# Mini_VFD_UI_RevA.net
KiCad netlist of a schematic drawn in EAGLE
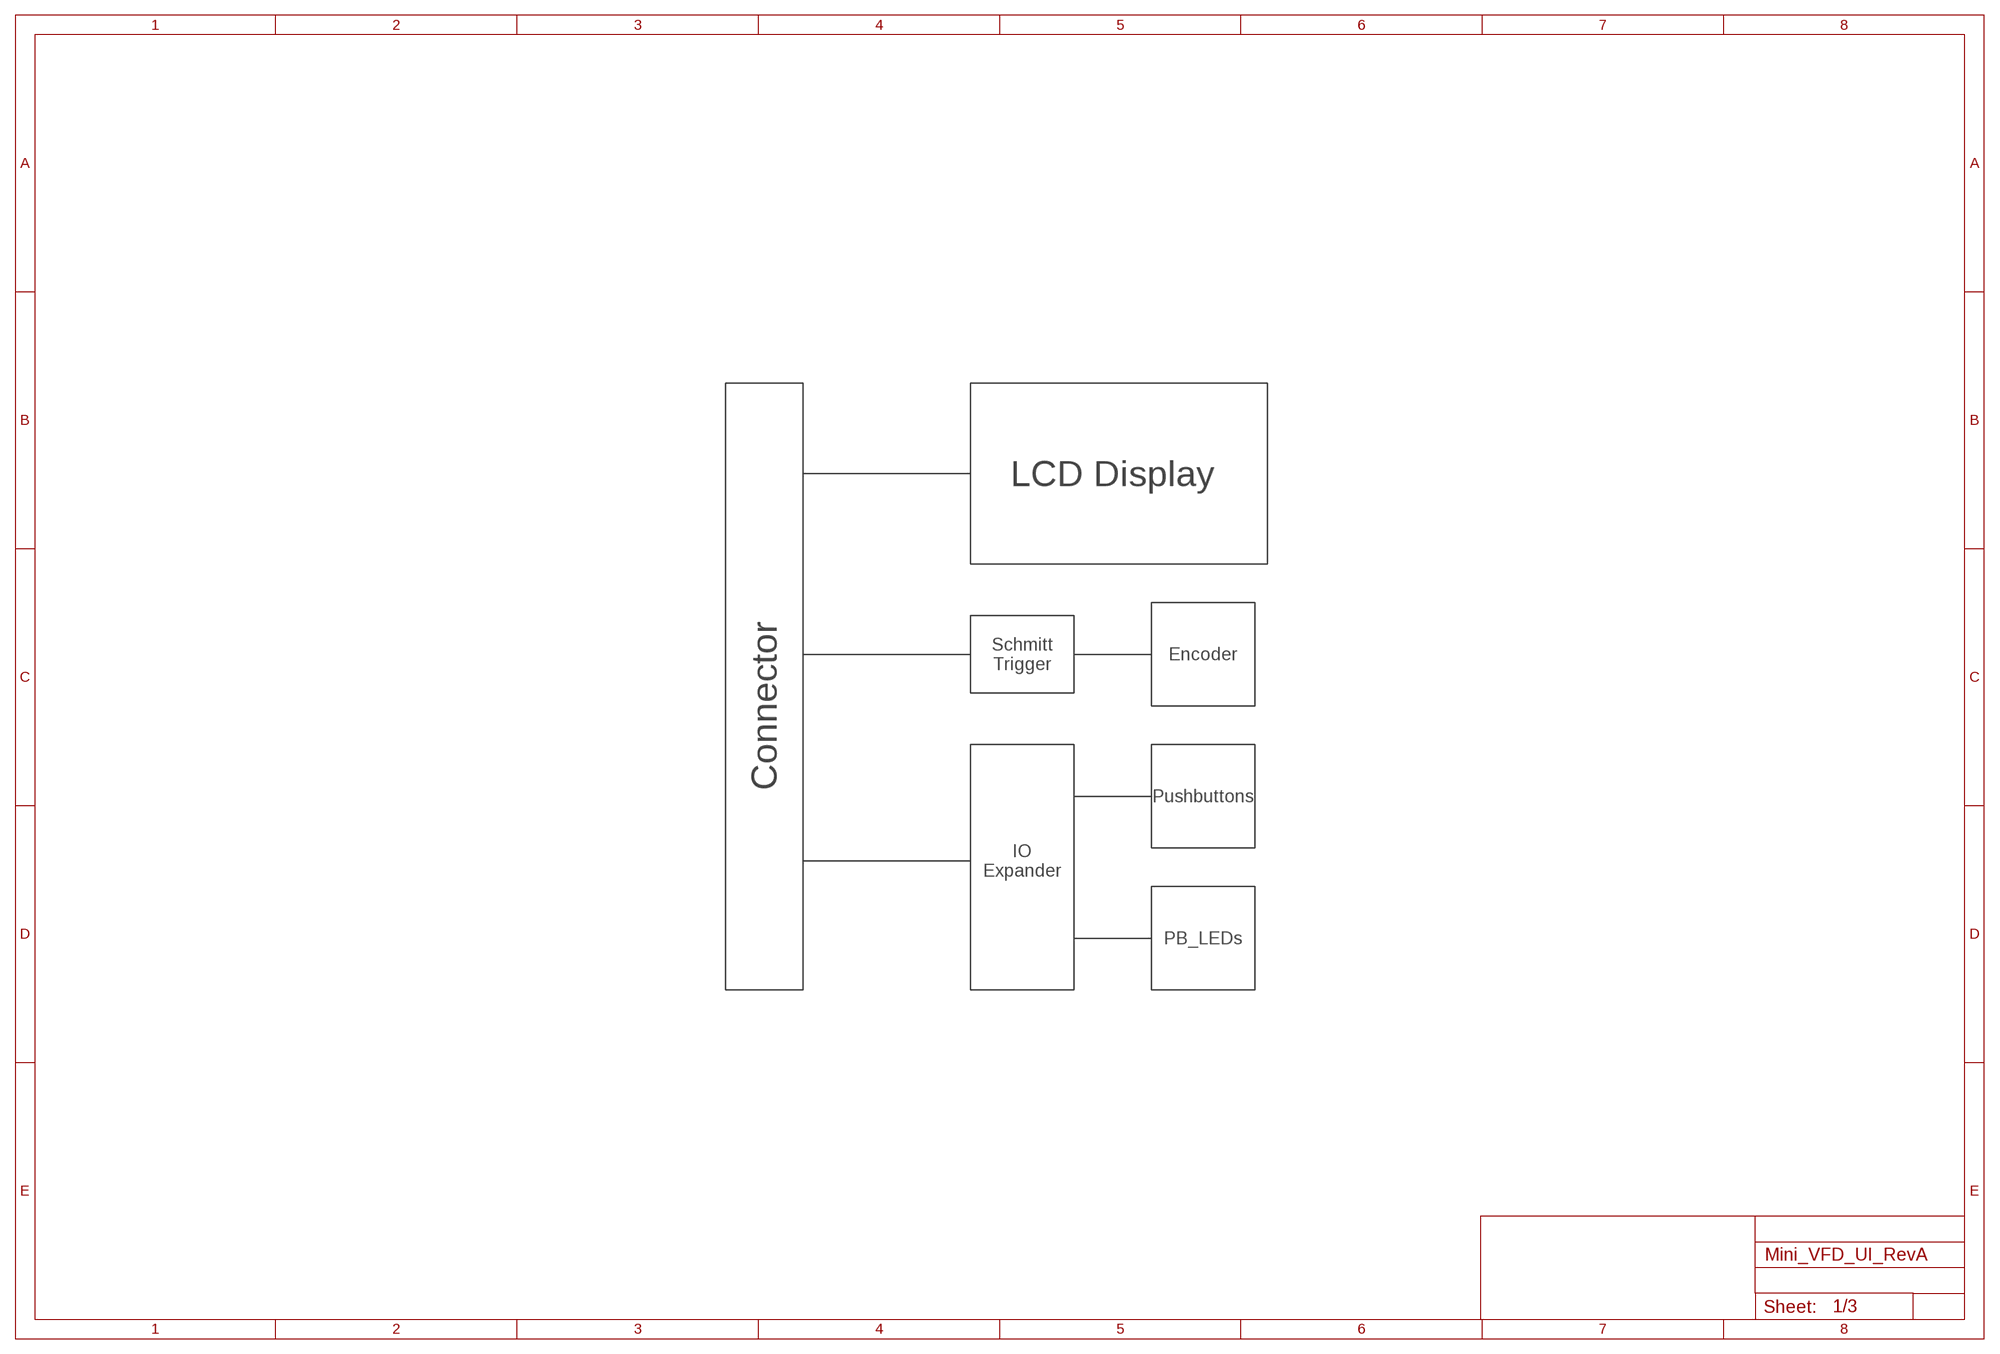
[diagram p0: schematic, sheet 1]
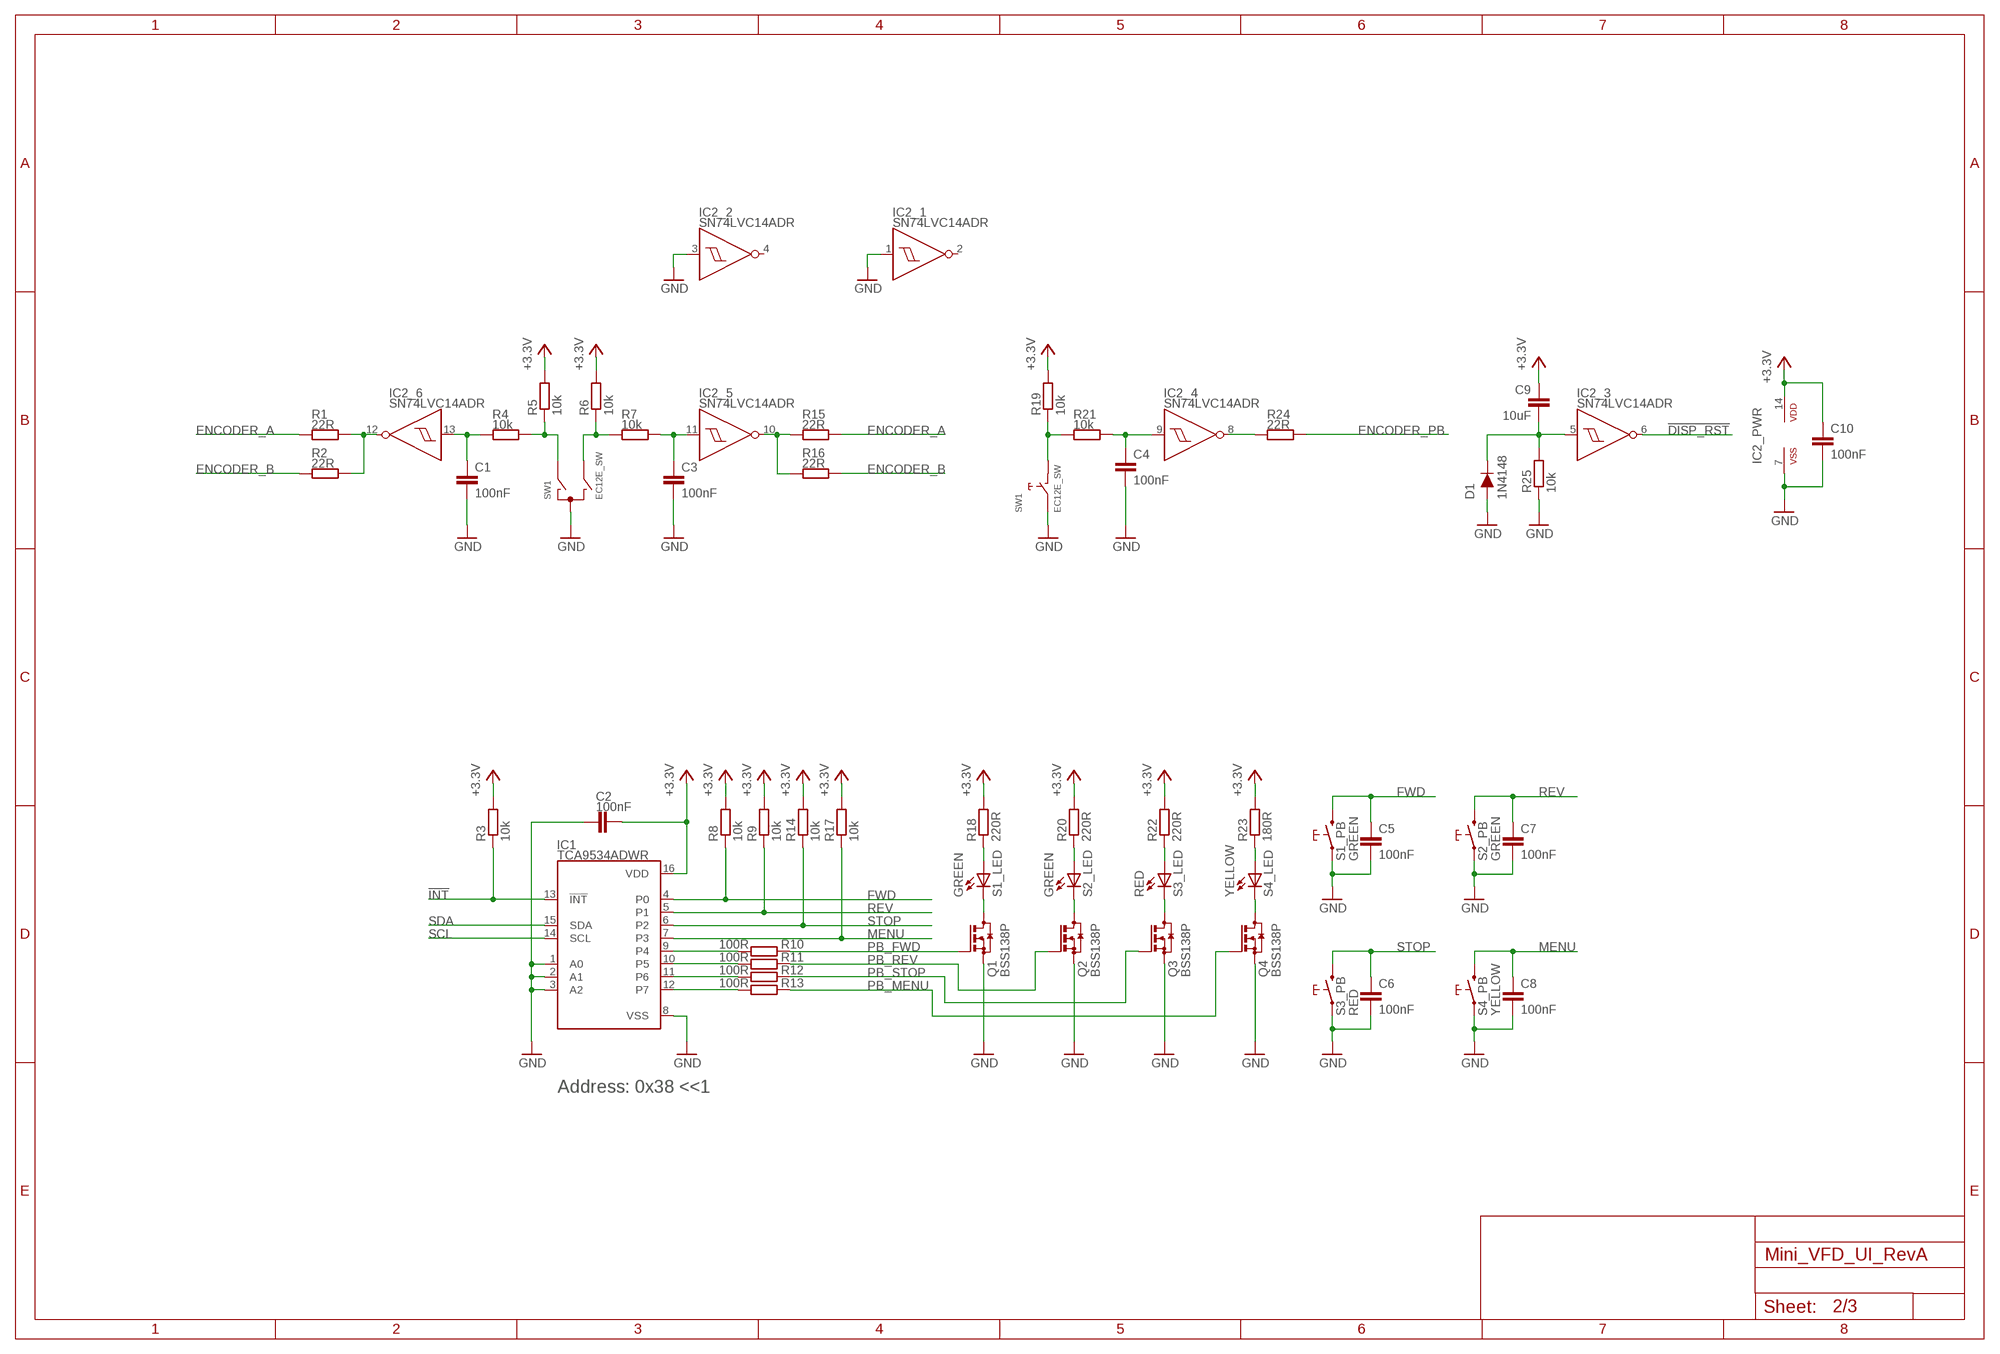
[diagram p1: schematic, sheet 2]
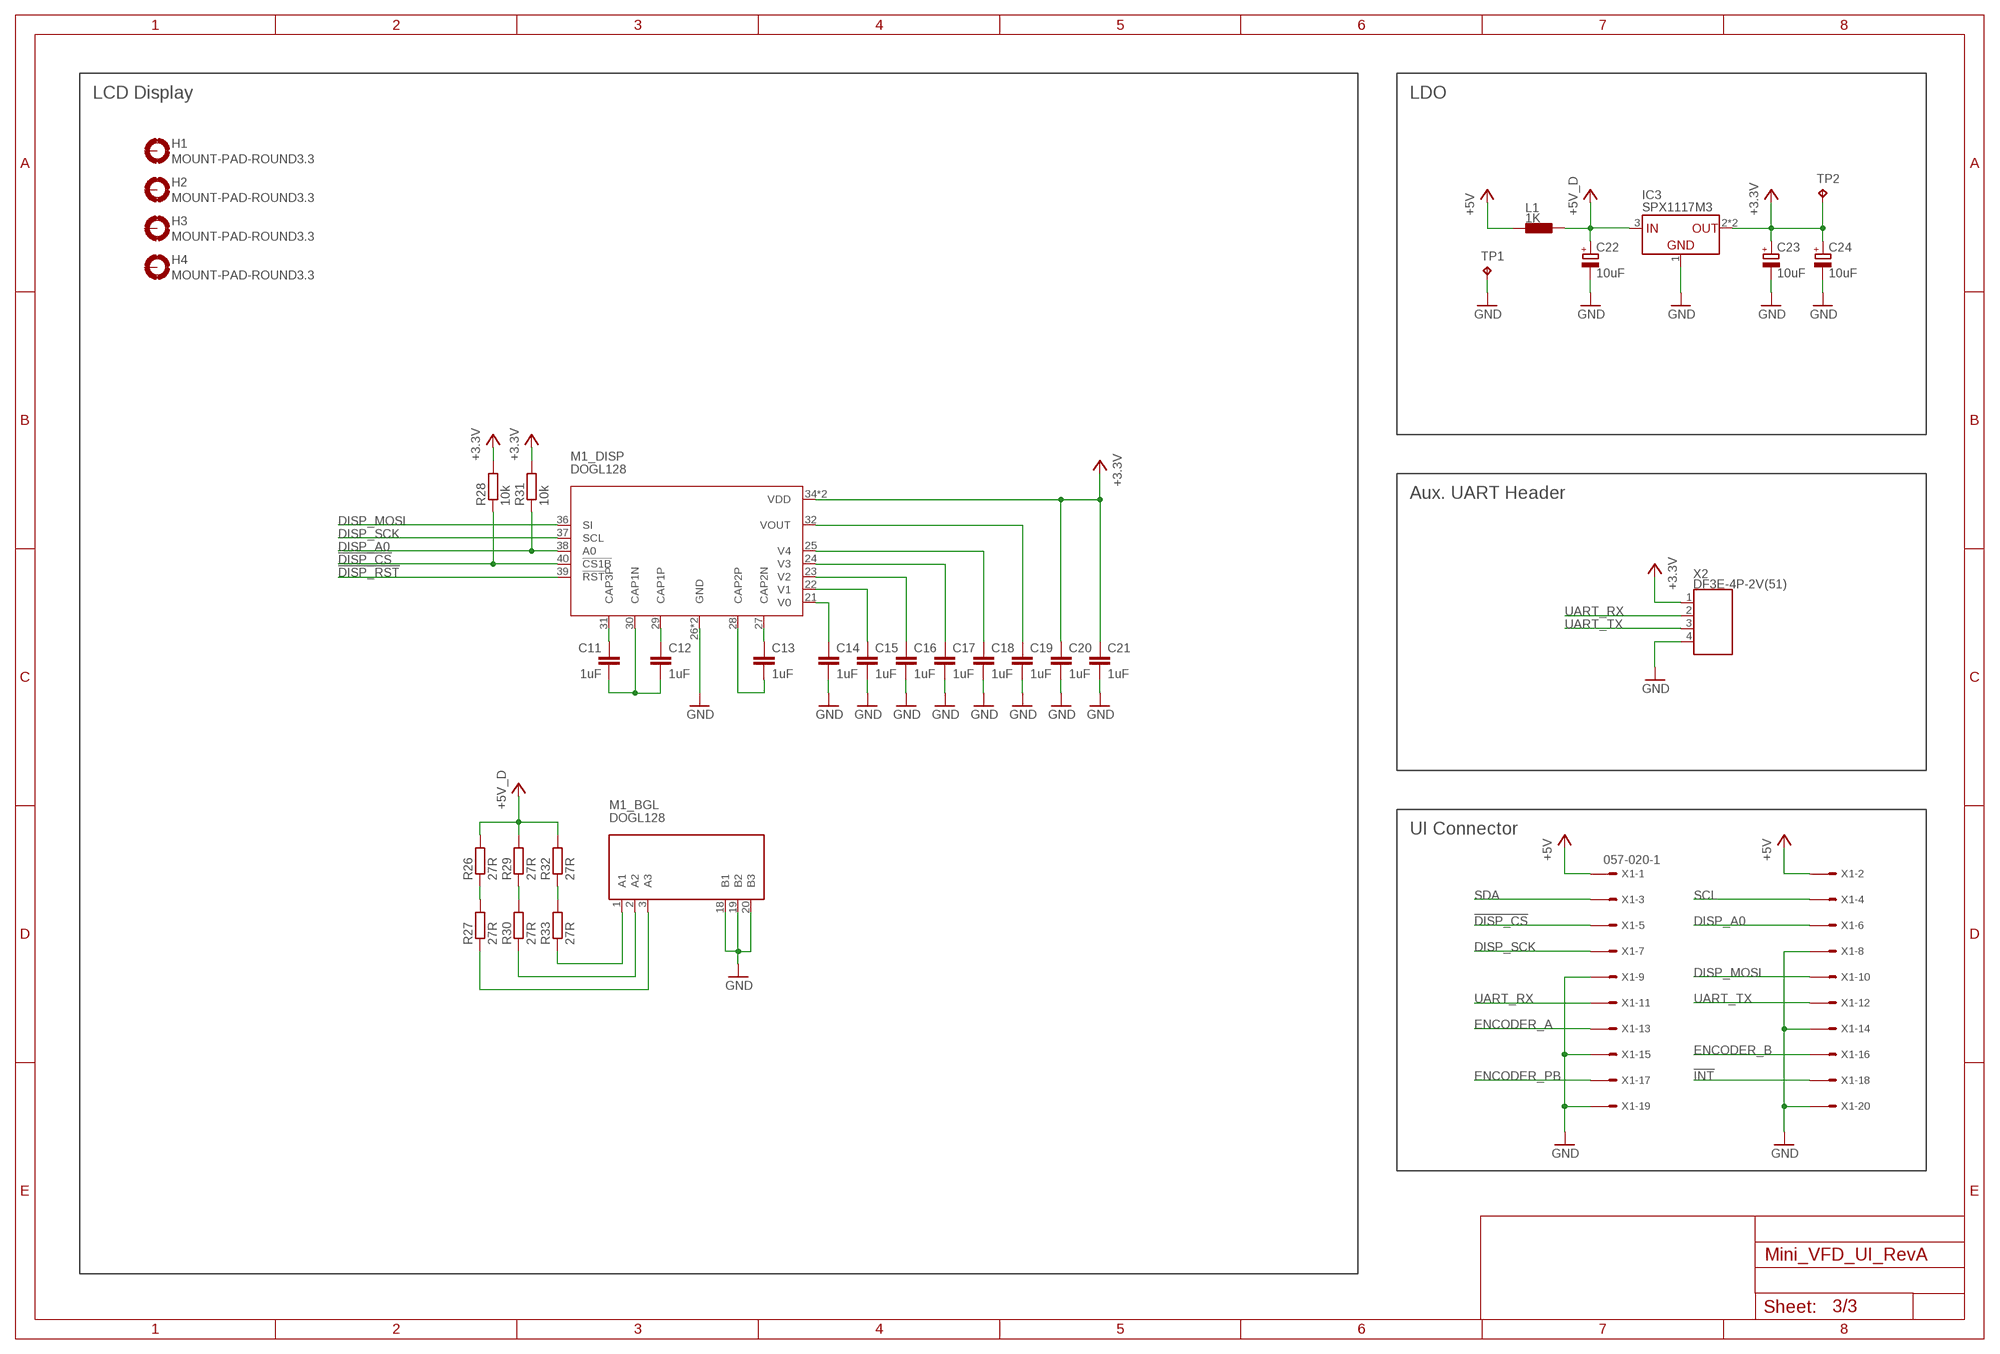
[diagram p2: schematic, sheet 3]

(export (version "E")
  (design (tool "Eeschema 10.0.6"))
  (components
    (comp (ref "C1")
      (value "100nF")
      (footprint "eagle-import:C0603")
      (libsource (lib "eagle-import") (part "C-EUC0603"))
    )
    (comp (ref "C2")
      (value "100nF")
      (footprint "eagle-import:C0603")
      (libsource (lib "eagle-import") (part "C-EUC0603"))
    )
    (comp (ref "C3")
      (value "100nF")
      (footprint "eagle-import:C0603")
      (libsource (lib "eagle-import") (part "C-EUC0603"))
    )
    (comp (ref "C4")
      (value "100nF")
      (footprint "eagle-import:C0603")
      (libsource (lib "eagle-import") (part "C-EUC0603"))
    )
    (comp (ref "C5")
      (value "100nF")
      (footprint "eagle-import:C0603")
      (libsource (lib "eagle-import") (part "C-EUC0603"))
    )
    (comp (ref "C6")
      (value "100nF")
      (footprint "eagle-import:C0603")
      (libsource (lib "eagle-import") (part "C-EUC0603"))
    )
    (comp (ref "C7")
      (value "100nF")
      (footprint "eagle-import:C0603")
      (libsource (lib "eagle-import") (part "C-EUC0603"))
    )
    (comp (ref "C8")
      (value "100nF")
      (footprint "eagle-import:C0603")
      (libsource (lib "eagle-import") (part "C-EUC0603"))
    )
    (comp (ref "C9")
      (value "10uF")
      (footprint "eagle-import:C1206")
      (libsource (lib "eagle-import") (part "C-EUC1206"))
    )
    (comp (ref "C10")
      (value "100nF")
      (footprint "eagle-import:C0603")
      (libsource (lib "eagle-import") (part "C-EUC0603"))
    )
    (comp (ref "D1")
      (value "1N4148")
      (footprint "eagle-import:SOD123")
      (libsource (lib "eagle-import") (part "DIODE"))
    )
    (comp (ref "IC1")
      (value "TCA9534ADWR")
      (footprint "eagle-import:SOIC16R")
      (libsource (lib "eagle-import") (part "TCA9534APWR_SOIC"))
    )
    (comp (ref "IC2")
      (value "SN74LVC14ADR")
      (footprint "eagle-import:SO14")
      (libsource (lib "eagle-import") (part "SN74AC14PWR_SOIC"))
    )
    (comp (ref "Q1")
      (value "BSS138P")
      (footprint "eagle-import:SOT23")
      (libsource (lib "eagle-import") (part "NMOS_BSS138P"))
    )
    (comp (ref "Q2")
      (value "BSS138P")
      (footprint "eagle-import:SOT23")
      (libsource (lib "eagle-import") (part "NMOS_BSS138P"))
    )
    (comp (ref "Q3")
      (value "BSS138P")
      (footprint "eagle-import:SOT23")
      (libsource (lib "eagle-import") (part "NMOS_BSS138P"))
    )
    (comp (ref "Q4")
      (value "BSS138P")
      (footprint "eagle-import:SOT23")
      (libsource (lib "eagle-import") (part "NMOS_BSS138P"))
    )
    (comp (ref "R1")
      (value "22R")
      (footprint "eagle-import:R0603")
      (libsource (lib "eagle-import") (part "R-EU_R0603"))
    )
    (comp (ref "R2")
      (value "22R")
      (footprint "eagle-import:R0603")
      (libsource (lib "eagle-import") (part "R-EU_R0603"))
    )
    (comp (ref "R3")
      (value "10k")
      (footprint "eagle-import:R0603")
      (libsource (lib "eagle-import") (part "R-EU_R0603"))
    )
    (comp (ref "R4")
      (value "10k")
      (footprint "eagle-import:R0603")
      (libsource (lib "eagle-import") (part "R-EU_R0603"))
    )
    (comp (ref "R5")
      (value "10k")
      (footprint "eagle-import:R0603")
      (libsource (lib "eagle-import") (part "R-EU_R0603"))
    )
    (comp (ref "R6")
      (value "10k")
      (footprint "eagle-import:R0603")
      (libsource (lib "eagle-import") (part "R-EU_R0603"))
    )
    (comp (ref "R7")
      (value "10k")
      (footprint "eagle-import:R0603")
      (libsource (lib "eagle-import") (part "R-EU_R0603"))
    )
    (comp (ref "R8")
      (value "10k")
      (footprint "eagle-import:R0603")
      (libsource (lib "eagle-import") (part "R-EU_R0603"))
    )
    (comp (ref "R9")
      (value "10k")
      (footprint "eagle-import:R0603")
      (libsource (lib "eagle-import") (part "R-EU_R0603"))
    )
    (comp (ref "R10")
      (value "100R")
      (footprint "eagle-import:R0603")
      (libsource (lib "eagle-import") (part "R-EU_R0603"))
    )
    (comp (ref "R11")
      (value "100R")
      (footprint "eagle-import:R0603")
      (libsource (lib "eagle-import") (part "R-EU_R0603"))
    )
    (comp (ref "R12")
      (value "100R")
      (footprint "eagle-import:R0603")
      (libsource (lib "eagle-import") (part "R-EU_R0603"))
    )
    (comp (ref "R13")
      (value "100R")
      (footprint "eagle-import:R0603")
      (libsource (lib "eagle-import") (part "R-EU_R0603"))
    )
    (comp (ref "R14")
      (value "10k")
      (footprint "eagle-import:R0603")
      (libsource (lib "eagle-import") (part "R-EU_R0603"))
    )
    (comp (ref "R15")
      (value "22R")
      (footprint "eagle-import:R0603")
      (libsource (lib "eagle-import") (part "R-EU_R0603"))
    )
    (comp (ref "R16")
      (value "22R")
      (footprint "eagle-import:R0603")
      (libsource (lib "eagle-import") (part "R-EU_R0603"))
    )
    (comp (ref "R17")
      (value "10k")
      (footprint "eagle-import:R0603")
      (libsource (lib "eagle-import") (part "R-EU_R0603"))
    )
    (comp (ref "R18")
      (value "220R")
      (footprint "eagle-import:R0603")
      (libsource (lib "eagle-import") (part "R-EU_R0603"))
    )
    (comp (ref "R19")
      (value "10k")
      (footprint "eagle-import:R0603")
      (libsource (lib "eagle-import") (part "R-EU_R0603"))
    )
    (comp (ref "R20")
      (value "220R")
      (footprint "eagle-import:R0603")
      (libsource (lib "eagle-import") (part "R-EU_R0603"))
    )
    (comp (ref "R21")
      (value "10k")
      (footprint "eagle-import:R0603")
      (libsource (lib "eagle-import") (part "R-EU_R0603"))
    )
    (comp (ref "R22")
      (value "220R")
      (footprint "eagle-import:R0603")
      (libsource (lib "eagle-import") (part "R-EU_R0603"))
    )
    (comp (ref "R23")
      (value "180R")
      (footprint "eagle-import:R0603")
      (libsource (lib "eagle-import") (part "R-EU_R0603"))
    )
    (comp (ref "R24")
      (value "22R")
      (footprint "eagle-import:R0603")
      (libsource (lib "eagle-import") (part "R-EU_R0603"))
    )
    (comp (ref "R25")
      (value "10k")
      (footprint "eagle-import:R0603")
      (libsource (lib "eagle-import") (part "R-EU_R0603"))
    )
    (comp (ref "S1")
      (value "GREEN")
      (footprint "eagle-import:PB_ALIEXPRESS")
      (libsource (lib "eagle-import") (part "PUSHBUTTON"))
    )
    (comp (ref "S2")
      (value "GREEN")
      (footprint "eagle-import:PB_ALIEXPRESS")
      (libsource (lib "eagle-import") (part "PUSHBUTTON"))
    )
    (comp (ref "S3")
      (value "RED")
      (footprint "eagle-import:PB_ALIEXPRESS")
      (libsource (lib "eagle-import") (part "PUSHBUTTON"))
    )
    (comp (ref "S4")
      (value "YELLOW")
      (footprint "eagle-import:PB_ALIEXPRESS")
      (libsource (lib "eagle-import") (part "PUSHBUTTON"))
    )
    (comp (ref "SW1")
      (value "EC12E_SW")
      (footprint "eagle-import:ALPS_EC12E_SW")
      (fields (field (name "MPN") "EC12E2424407"))
      (libsource (lib "eagle-import") (part "EC12E_SW"))
    )
    (comp (ref "C11")
      (value "1uF")
      (footprint "eagle-import:C0603")
      (libsource (lib "eagle-import") (part "C-EUC0603"))
    )
    (comp (ref "C12")
      (value "1uF")
      (footprint "eagle-import:C0603")
      (libsource (lib "eagle-import") (part "C-EUC0603"))
    )
    (comp (ref "C13")
      (value "1uF")
      (footprint "eagle-import:C0603")
      (libsource (lib "eagle-import") (part "C-EUC0603"))
    )
    (comp (ref "C14")
      (value "1uF")
      (footprint "eagle-import:C0603")
      (libsource (lib "eagle-import") (part "C-EUC0603"))
    )
    (comp (ref "C15")
      (value "1uF")
      (footprint "eagle-import:C0603")
      (libsource (lib "eagle-import") (part "C-EUC0603"))
    )
    (comp (ref "C16")
      (value "1uF")
      (footprint "eagle-import:C0603")
      (libsource (lib "eagle-import") (part "C-EUC0603"))
    )
    (comp (ref "C17")
      (value "1uF")
      (footprint "eagle-import:C0603")
      (libsource (lib "eagle-import") (part "C-EUC0603"))
    )
    (comp (ref "C18")
      (value "1uF")
      (footprint "eagle-import:C0603")
      (libsource (lib "eagle-import") (part "C-EUC0603"))
    )
    (comp (ref "C19")
      (value "1uF")
      (footprint "eagle-import:C0603")
      (libsource (lib "eagle-import") (part "C-EUC0603"))
    )
    (comp (ref "C20")
      (value "1uF")
      (footprint "eagle-import:C0603")
      (libsource (lib "eagle-import") (part "C-EUC0603"))
    )
    (comp (ref "C21")
      (value "1uF")
      (footprint "eagle-import:C0603")
      (libsource (lib "eagle-import") (part "C-EUC0603"))
    )
    (comp (ref "C22")
      (value "10uF")
      (footprint "eagle-import:CT3528")
      (libsource (lib "eagle-import") (part "CPOL-EUCT3528"))
    )
    (comp (ref "C23")
      (value "10uF")
      (footprint "eagle-import:CT3528")
      (libsource (lib "eagle-import") (part "CPOL-EUCT3528"))
    )
    (comp (ref "C24")
      (value "10uF")
      (footprint "eagle-import:CT3528")
      (libsource (lib "eagle-import") (part "CPOL-EUCT3528"))
    )
    (comp (ref "H1")
      (value "MOUNT-PAD-ROUND3.3")
      (footprint "eagle-import:3,3-PAD")
      (libsource (lib "eagle-import") (part "MOUNT-PAD-ROUND3.3"))
    )
    (comp (ref "H2")
      (value "MOUNT-PAD-ROUND3.3")
      (footprint "eagle-import:3,3-PAD")
      (libsource (lib "eagle-import") (part "MOUNT-PAD-ROUND3.3"))
    )
    (comp (ref "H3")
      (value "MOUNT-PAD-ROUND3.3")
      (footprint "eagle-import:3,3-PAD")
      (libsource (lib "eagle-import") (part "MOUNT-PAD-ROUND3.3"))
    )
    (comp (ref "H4")
      (value "MOUNT-PAD-ROUND3.3")
      (footprint "eagle-import:3,3-PAD")
      (libsource (lib "eagle-import") (part "MOUNT-PAD-ROUND3.3"))
    )
    (comp (ref "IC3")
      (value "SPX1117M3")
      (footprint "eagle-import:SOT223")
      (libsource (lib "eagle-import") (part "SPX1117_3V3"))
    )
    (comp (ref "L1")
      (value "1K")
      (footprint "eagle-import:R0603")
      (libsource (lib "eagle-import") (part "BEAD0603"))
    )
    (comp (ref "M1")
      (value "DOGL128")
      (footprint "eagle-import:DOGL128-6")
      (libsource (lib "eagle-import") (part "DOGL128"))
    )
    (comp (ref "R26")
      (value "27R")
      (footprint "eagle-import:R1206")
      (libsource (lib "eagle-import") (part "R-EU_R1206"))
    )
    (comp (ref "R27")
      (value "27R")
      (footprint "eagle-import:R1206")
      (libsource (lib "eagle-import") (part "R-EU_R1206"))
    )
    (comp (ref "R28")
      (value "10k")
      (footprint "eagle-import:R0603")
      (libsource (lib "eagle-import") (part "R-EU_R0603"))
    )
    (comp (ref "R29")
      (value "27R")
      (footprint "eagle-import:R1206")
      (libsource (lib "eagle-import") (part "R-EU_R1206"))
    )
    (comp (ref "R30")
      (value "27R")
      (footprint "eagle-import:R1206")
      (libsource (lib "eagle-import") (part "R-EU_R1206"))
    )
    (comp (ref "R31")
      (value "10k")
      (footprint "eagle-import:R0603")
      (libsource (lib "eagle-import") (part "R-EU_R0603"))
    )
    (comp (ref "R32")
      (value "27R")
      (footprint "eagle-import:R1206")
      (libsource (lib "eagle-import") (part "R-EU_R1206"))
    )
    (comp (ref "R33")
      (value "27R")
      (footprint "eagle-import:R1206")
      (libsource (lib "eagle-import") (part "R-EU_R1206"))
    )
    (comp (ref "TP1")
      (value "TPTP10R")
      (footprint "eagle-import:TP10R")
      (libsource (lib "eagle-import") (part "TPTP10R"))
    )
    (comp (ref "TP2")
      (value "TPTP10R")
      (footprint "eagle-import:TP10R")
      (libsource (lib "eagle-import") (part "TPTP10R"))
    )
    (comp (ref "X1")
      (value "057-020-1")
      (footprint "eagle-import:057-020-1")
      (libsource (lib "eagle-import") (part "057-020-1"))
    )
    (comp (ref "X2")
      (value "DF3E-4P-2V(51)")
      (footprint "eagle-import:DF3E-4P-2V")
      (libsource (lib "eagle-import") (part "DF3E-4P-2V"))
    )
  )
  (nets
    (net (code "1") (name "+3.3V") (class "Default")
      (node (ref "C10") (pin "1") (pinfunction "1_1") (pintype "passive"))
      (node (ref "C2") (pin "2") (pinfunction "2_2") (pintype "passive"))
      (node (ref "C20") (pin "1") (pinfunction "1_1") (pintype "passive"))
      (node (ref "C21") (pin "1") (pinfunction "1_1") (pintype "passive"))
      (node (ref "C23") (pin "+") (pinfunction "+_+") (pintype "passive"))
      (node (ref "C24") (pin "+") (pinfunction "+_+") (pintype "passive"))
      (node (ref "C9") (pin "1") (pinfunction "1_1") (pintype "passive"))
      (node (ref "IC1") (pin "16") (pinfunction "VDD_16") (pintype "input"))
      (node (ref "IC2") (pin "14") (pinfunction "VDD_14") (pintype "input"))
      (node (ref "IC3") (pin "2") (pinfunction "VOUT_2") (pintype "input"))
      (node (ref "IC3") (pin "4") (pinfunction "VOUT_4") (pintype "input"))
      (node (ref "M1") (pin "34") (pinfunction "VDD_34") (pintype "bidirectional"))
      (node (ref "M1") (pin "35") (pinfunction "VDD_35") (pintype "bidirectional"))
      (node (ref "R14") (pin "2") (pinfunction "2_2") (pintype "passive"))
      (node (ref "R17") (pin "2") (pinfunction "2_2") (pintype "passive"))
      (node (ref "R18") (pin "2") (pinfunction "2_2") (pintype "passive"))
      (node (ref "R19") (pin "2") (pinfunction "2_2") (pintype "passive"))
      (node (ref "R20") (pin "2") (pinfunction "2_2") (pintype "passive"))
      (node (ref "R22") (pin "2") (pinfunction "2_2") (pintype "passive"))
      (node (ref "R23") (pin "2") (pinfunction "2_2") (pintype "passive"))
      (node (ref "R28") (pin "2") (pinfunction "2_2") (pintype "passive"))
      (node (ref "R3") (pin "2") (pinfunction "2_2") (pintype "passive"))
      (node (ref "R31") (pin "2") (pinfunction "2_2") (pintype "passive"))
      (node (ref "R5") (pin "2") (pinfunction "2_2") (pintype "passive"))
      (node (ref "R6") (pin "2") (pinfunction "2_2") (pintype "passive"))
      (node (ref "R8") (pin "2") (pinfunction "2_2") (pintype "passive"))
      (node (ref "R9") (pin "2") (pinfunction "2_2") (pintype "passive"))
      (node (ref "TP2") (pin "TP") (pinfunction "TP_TP") (pintype "input"))
      (node (ref "X2") (pin "1") (pinfunction "1_1") (pintype "passive"))
    )
    (net (code "2") (name "+5V") (class "Default")
      (node (ref "L1") (pin "2") (pinfunction "2_2") (pintype "passive"))
      (node (ref "X1") (pin "1") (pinfunction "S_1") (pintype "passive"))
      (node (ref "X1") (pin "2") (pinfunction "S_2") (pintype "passive"))
    )
    (net (code "3") (name "+5V_D") (class "Default")
      (node (ref "C22") (pin "+") (pinfunction "+_+") (pintype "passive"))
      (node (ref "IC3") (pin "3") (pinfunction "VIN_3") (pintype "input"))
      (node (ref "L1") (pin "1") (pinfunction "1_1") (pintype "passive"))
      (node (ref "R26") (pin "2") (pinfunction "2_2") (pintype "passive"))
      (node (ref "R29") (pin "2") (pinfunction "2_2") (pintype "passive"))
      (node (ref "R32") (pin "2") (pinfunction "2_2") (pintype "passive"))
    )
    (net (code "4") (name "DISP_A0") (class "Default")
      (node (ref "M1") (pin "38") (pinfunction "A0_38") (pintype "bidirectional"))
      (node (ref "R31") (pin "1") (pinfunction "1_1") (pintype "passive"))
      (node (ref "X1") (pin "6") (pinfunction "S_6") (pintype "passive"))
    )
    (net (code "5") (name "DISP_MOSI") (class "Default")
      (node (ref "M1") (pin "36") (pinfunction "SI_36") (pintype "bidirectional"))
      (node (ref "X1") (pin "10") (pinfunction "S_10") (pintype "passive"))
    )
    (net (code "6") (name "DISP_SCK") (class "Default")
      (node (ref "M1") (pin "37") (pinfunction "SCL_37") (pintype "bidirectional"))
      (node (ref "X1") (pin "7") (pinfunction "S_7") (pintype "passive"))
    )
    (net (code "7") (name "ENCODER_A") (class "Default")
      (node (ref "R1") (pin "1") (pinfunction "1_1") (pintype "passive"))
      (node (ref "R15") (pin "2") (pinfunction "2_2") (pintype "passive"))
      (node (ref "X1") (pin "13") (pinfunction "S_13") (pintype "passive"))
    )
    (net (code "8") (name "ENCODER_B") (class "Default")
      (node (ref "R16") (pin "2") (pinfunction "2_2") (pintype "passive"))
      (node (ref "R2") (pin "1") (pinfunction "1_1") (pintype "passive"))
      (node (ref "X1") (pin "16") (pinfunction "S_16") (pintype "passive"))
    )
    (net (code "9") (name "ENCODER_PB") (class "Default")
      (node (ref "R24") (pin "2") (pinfunction "2_2") (pintype "passive"))
      (node (ref "X1") (pin "17") (pinfunction "S_17") (pintype "passive"))
    )
    (net (code "10") (name "FWD") (class "Default")
      (node (ref "C5") (pin "1") (pinfunction "1_1") (pintype "passive"))
      (node (ref "IC1") (pin "4") (pinfunction "P0_4") (pintype "bidirectional"))
      (node (ref "R8") (pin "1") (pinfunction "1_1") (pintype "passive"))
      (node (ref "S1") (pin "2A") (pinfunction "2_2A") (pintype "passive"))
      (node (ref "S1") (pin "2B") (pinfunction "2_2B") (pintype "passive"))
    )
    (net (code "11") (name "GND") (class "Default")
      (node (ref "C1") (pin "2") (pinfunction "2_2") (pintype "passive"))
      (node (ref "C10") (pin "2") (pinfunction "2_2") (pintype "passive"))
      (node (ref "C14") (pin "2") (pinfunction "2_2") (pintype "passive"))
      (node (ref "C15") (pin "2") (pinfunction "2_2") (pintype "passive"))
      (node (ref "C16") (pin "2") (pinfunction "2_2") (pintype "passive"))
      (node (ref "C17") (pin "2") (pinfunction "2_2") (pintype "passive"))
      (node (ref "C18") (pin "2") (pinfunction "2_2") (pintype "passive"))
      (node (ref "C19") (pin "2") (pinfunction "2_2") (pintype "passive"))
      (node (ref "C2") (pin "1") (pinfunction "1_1") (pintype "passive"))
      (node (ref "C20") (pin "2") (pinfunction "2_2") (pintype "passive"))
      (node (ref "C21") (pin "2") (pinfunction "2_2") (pintype "passive"))
      (node (ref "C22") (pin "-") (pinfunction "-_-") (pintype "passive"))
      (node (ref "C23") (pin "-") (pinfunction "-_-") (pintype "passive"))
      (node (ref "C24") (pin "-") (pinfunction "-_-") (pintype "passive"))
      (node (ref "C3") (pin "2") (pinfunction "2_2") (pintype "passive"))
      (node (ref "C4") (pin "2") (pinfunction "2_2") (pintype "passive"))
      (node (ref "C5") (pin "2") (pinfunction "2_2") (pintype "passive"))
      (node (ref "C6") (pin "2") (pinfunction "2_2") (pintype "passive"))
      (node (ref "C7") (pin "2") (pinfunction "2_2") (pintype "passive"))
      (node (ref "C8") (pin "2") (pinfunction "2_2") (pintype "passive"))
      (node (ref "D1") (pin "2") (pinfunction "A_2") (pintype "passive"))
      (node (ref "IC1") (pin "1") (pinfunction "A0_1") (pintype "input"))
      (node (ref "IC1") (pin "2") (pinfunction "A1_2") (pintype "input"))
      (node (ref "IC1") (pin "3") (pinfunction "A2_3") (pintype "input"))
      (node (ref "IC1") (pin "8") (pinfunction "VSS_8") (pintype "input"))
      (node (ref "IC2") (pin "1") (pinfunction "I_1") (pintype "input"))
      (node (ref "IC2") (pin "3") (pinfunction "I_3") (pintype "input"))
      (node (ref "IC2") (pin "7") (pinfunction "VSS_7") (pintype "input"))
      (node (ref "IC3") (pin "1") (pinfunction "GND_1") (pintype "input"))
      (node (ref "M1") (pin "18") (pinfunction "B1_18") (pintype "bidirectional"))
      (node (ref "M1") (pin "19") (pinfunction "B2_19") (pintype "bidirectional"))
      (node (ref "M1") (pin "20") (pinfunction "B3_20") (pintype "bidirectional"))
      (node (ref "M1") (pin "26") (pinfunction "GND_26") (pintype "bidirectional"))
      (node (ref "M1") (pin "33") (pinfunction "GND_33") (pintype "bidirectional"))
      (node (ref "Q1") (pin "2") (pinfunction "S_2") (pintype "passive"))
      (node (ref "Q2") (pin "2") (pinfunction "S_2") (pintype "passive"))
      (node (ref "Q3") (pin "2") (pinfunction "S_2") (pintype "passive"))
      (node (ref "Q4") (pin "2") (pinfunction "S_2") (pintype "passive"))
      (node (ref "R25") (pin "1") (pinfunction "1_1") (pintype "passive"))
      (node (ref "S1") (pin "1A") (pinfunction "1_1A") (pintype "passive"))
      (node (ref "S1") (pin "1B") (pinfunction "1_1B") (pintype "passive"))
      (node (ref "S2") (pin "1A") (pinfunction "1_1A") (pintype "passive"))
      (node (ref "S2") (pin "1B") (pinfunction "1_1B") (pintype "passive"))
      (node (ref "S3") (pin "1A") (pinfunction "1_1A") (pintype "passive"))
      (node (ref "S3") (pin "1B") (pinfunction "1_1B") (pintype "passive"))
      (node (ref "S4") (pin "1A") (pinfunction "1_1A") (pintype "passive"))
      (node (ref "S4") (pin "1B") (pinfunction "1_1B") (pintype "passive"))
      (node (ref "SW1") (pin "C") (pinfunction "C_C") (pintype "passive"))
      (node (ref "SW1") (pin "E") (pinfunction "2_E") (pintype "passive"))
      (node (ref "TP1") (pin "TP") (pinfunction "TP_TP") (pintype "input"))
      (node (ref "X1") (pin "14") (pinfunction "S_14") (pintype "passive"))
      (node (ref "X1") (pin "15") (pinfunction "S_15") (pintype "passive"))
      (node (ref "X1") (pin "19") (pinfunction "S_19") (pintype "passive"))
      (node (ref "X1") (pin "20") (pinfunction "S_20") (pintype "passive"))
      (node (ref "X1") (pin "8") (pinfunction "S_8") (pintype "passive"))
      (node (ref "X1") (pin "9") (pinfunction "S_9") (pintype "passive"))
      (node (ref "X2") (pin "4") (pinfunction "4_4") (pintype "passive"))
    )
    (net (code "12") (name "MENU") (class "Default")
      (node (ref "C8") (pin "1") (pinfunction "1_1") (pintype "passive"))
      (node (ref "IC1") (pin "7") (pinfunction "P3_7") (pintype "bidirectional"))
      (node (ref "R17") (pin "1") (pinfunction "1_1") (pintype "passive"))
      (node (ref "S4") (pin "2A") (pinfunction "2_2A") (pintype "passive"))
      (node (ref "S4") (pin "2B") (pinfunction "2_2B") (pintype "passive"))
    )
    (net (code "13") (name "Net-(D1-C)") (class "Default")
      (node (ref "C9") (pin "2") (pinfunction "2_2") (pintype "passive"))
      (node (ref "D1") (pin "1") (pinfunction "C_1") (pintype "passive"))
      (node (ref "IC2") (pin "5") (pinfunction "I_5") (pintype "input"))
      (node (ref "R25") (pin "2") (pinfunction "2_2") (pintype "passive"))
    )
    (net (code "14") (name "Net-(IC1-P4)") (class "Default")
      (node (ref "IC1") (pin "9") (pinfunction "P4_9") (pintype "bidirectional"))
      (node (ref "R10") (pin "1") (pinfunction "1_1") (pintype "passive"))
    )
    (net (code "15") (name "Net-(IC1-P5)") (class "Default")
      (node (ref "IC1") (pin "10") (pinfunction "P5_10") (pintype "bidirectional"))
      (node (ref "R11") (pin "1") (pinfunction "1_1") (pintype "passive"))
    )
    (net (code "16") (name "Net-(IC1-P6)") (class "Default")
      (node (ref "IC1") (pin "11") (pinfunction "P6_11") (pintype "bidirectional"))
      (node (ref "R12") (pin "1") (pinfunction "1_1") (pintype "passive"))
    )
    (net (code "17") (name "Net-(IC1-P7)") (class "Default")
      (node (ref "IC1") (pin "12") (pinfunction "P7_12") (pintype "bidirectional"))
      (node (ref "R13") (pin "1") (pinfunction "1_1") (pintype "passive"))
    )
    (net (code "18") (name "Net-(IC2D-I)") (class "Default")
      (node (ref "C4") (pin "1") (pinfunction "1_1") (pintype "passive"))
      (node (ref "IC2") (pin "9") (pinfunction "I_9") (pintype "input"))
      (node (ref "R21") (pin "2") (pinfunction "2_2") (pintype "passive"))
    )
    (net (code "19") (name "Net-(IC2D-O)") (class "Default")
      (node (ref "IC2") (pin "8") (pinfunction "O_8") (pintype "output"))
      (node (ref "R24") (pin "1") (pinfunction "1_1") (pintype "passive"))
    )
    (net (code "20") (name "Net-(IC2E-I)") (class "Default")
      (node (ref "C3") (pin "1") (pinfunction "1_1") (pintype "passive"))
      (node (ref "IC2") (pin "11") (pinfunction "I_11") (pintype "input"))
      (node (ref "R7") (pin "2") (pinfunction "2_2") (pintype "passive"))
    )
    (net (code "21") (name "Net-(IC2E-O)") (class "Default")
      (node (ref "IC2") (pin "10") (pinfunction "O_10") (pintype "output"))
      (node (ref "R15") (pin "1") (pinfunction "1_1") (pintype "passive"))
      (node (ref "R16") (pin "1") (pinfunction "1_1") (pintype "passive"))
    )
    (net (code "22") (name "Net-(IC2F-I)") (class "Default")
      (node (ref "C1") (pin "1") (pinfunction "1_1") (pintype "passive"))
      (node (ref "IC2") (pin "13") (pinfunction "I_13") (pintype "input"))
      (node (ref "R4") (pin "1") (pinfunction "1_1") (pintype "passive"))
    )
    (net (code "23") (name "Net-(IC2F-O)") (class "Default")
      (node (ref "IC2") (pin "12") (pinfunction "O_12") (pintype "output"))
      (node (ref "R1") (pin "2") (pinfunction "2_2") (pintype "passive"))
      (node (ref "R2") (pin "2") (pinfunction "2_2") (pintype "passive"))
    )
    (net (code "24") (name "Net-(M1A-A1)") (class "Default")
      (node (ref "M1") (pin "1") (pinfunction "A1_1") (pintype "bidirectional"))
      (node (ref "R33") (pin "1") (pinfunction "1_1") (pintype "passive"))
    )
    (net (code "25") (name "Net-(M1A-A2)") (class "Default")
      (node (ref "M1") (pin "2") (pinfunction "A2_2") (pintype "bidirectional"))
      (node (ref "R30") (pin "1") (pinfunction "1_1") (pintype "passive"))
    )
    (net (code "26") (name "Net-(M1A-A3)") (class "Default")
      (node (ref "M1") (pin "3") (pinfunction "A3_3") (pintype "bidirectional"))
      (node (ref "R27") (pin "1") (pinfunction "1_1") (pintype "passive"))
    )
    (net (code "27") (name "Net-(M1B-CAP1N)") (class "Default")
      (node (ref "C11") (pin "2") (pinfunction "2_2") (pintype "passive"))
      (node (ref "C12") (pin "2") (pinfunction "2_2") (pintype "passive"))
      (node (ref "M1") (pin "30") (pinfunction "CAP1N_30") (pintype "bidirectional"))
    )
    (net (code "28") (name "Net-(M1B-CAP1P)") (class "Default")
      (node (ref "C12") (pin "1") (pinfunction "1_1") (pintype "passive"))
      (node (ref "M1") (pin "29") (pinfunction "CAP1P_29") (pintype "bidirectional"))
    )
    (net (code "29") (name "Net-(M1B-CAP2N)") (class "Default")
      (node (ref "C13") (pin "1") (pinfunction "1_1") (pintype "passive"))
      (node (ref "M1") (pin "27") (pinfunction "CAP2N_27") (pintype "bidirectional"))
    )
    (net (code "30") (name "Net-(M1B-CAP2P)") (class "Default")
      (node (ref "C13") (pin "2") (pinfunction "2_2") (pintype "passive"))
      (node (ref "M1") (pin "28") (pinfunction "CAP2P_28") (pintype "bidirectional"))
    )
    (net (code "31") (name "Net-(M1B-CAP3P)") (class "Default")
      (node (ref "C11") (pin "1") (pinfunction "1_1") (pintype "passive"))
      (node (ref "M1") (pin "31") (pinfunction "CAP3P_31") (pintype "bidirectional"))
    )
    (net (code "32") (name "Net-(M1B-V0)") (class "Default")
      (node (ref "C14") (pin "1") (pinfunction "1_1") (pintype "passive"))
      (node (ref "M1") (pin "21") (pinfunction "V0_21") (pintype "bidirectional"))
    )
    (net (code "33") (name "Net-(M1B-V1)") (class "Default")
      (node (ref "C15") (pin "1") (pinfunction "1_1") (pintype "passive"))
      (node (ref "M1") (pin "22") (pinfunction "V1_22") (pintype "bidirectional"))
    )
    (net (code "34") (name "Net-(M1B-V2)") (class "Default")
      (node (ref "C16") (pin "1") (pinfunction "1_1") (pintype "passive"))
      (node (ref "M1") (pin "23") (pinfunction "V2_23") (pintype "bidirectional"))
    )
    (net (code "35") (name "Net-(M1B-V3)") (class "Default")
      (node (ref "C17") (pin "1") (pinfunction "1_1") (pintype "passive"))
      (node (ref "M1") (pin "24") (pinfunction "V3_24") (pintype "bidirectional"))
    )
    (net (code "36") (name "Net-(M1B-V4)") (class "Default")
      (node (ref "C18") (pin "1") (pinfunction "1_1") (pintype "passive"))
      (node (ref "M1") (pin "25") (pinfunction "V4_25") (pintype "bidirectional"))
    )
    (net (code "37") (name "Net-(M1B-VOUT)") (class "Default")
      (node (ref "C19") (pin "1") (pinfunction "1_1") (pintype "passive"))
      (node (ref "M1") (pin "32") (pinfunction "VOUT_32") (pintype "bidirectional"))
    )
    (net (code "38") (name "Net-(Q1-D)") (class "Default")
      (node (ref "Q1") (pin "3") (pinfunction "D_3") (pintype "passive"))
      (node (ref "S1") (pin "-") (pinfunction "C_-") (pintype "passive"))
    )
    (net (code "39") (name "Net-(Q2-D)") (class "Default")
      (node (ref "Q2") (pin "3") (pinfunction "D_3") (pintype "passive"))
      (node (ref "S2") (pin "-") (pinfunction "C_-") (pintype "passive"))
    )
    (net (code "40") (name "Net-(Q3-D)") (class "Default")
      (node (ref "Q3") (pin "3") (pinfunction "D_3") (pintype "passive"))
      (node (ref "S3") (pin "-") (pinfunction "C_-") (pintype "passive"))
    )
    (net (code "41") (name "Net-(Q4-D)") (class "Default")
      (node (ref "Q4") (pin "3") (pinfunction "D_3") (pintype "passive"))
      (node (ref "S4") (pin "-") (pinfunction "C_-") (pintype "passive"))
    )
    (net (code "42") (name "Net-(R4-Pad2)") (class "Default")
      (node (ref "R4") (pin "2") (pinfunction "2_2") (pintype "passive"))
      (node (ref "R5") (pin "1") (pinfunction "1_1") (pintype "passive"))
      (node (ref "SW1") (pin "A") (pinfunction "A_A") (pintype "passive"))
    )
    (net (code "43") (name "Net-(R6-Pad1)") (class "Default")
      (node (ref "R6") (pin "1") (pinfunction "1_1") (pintype "passive"))
      (node (ref "R7") (pin "1") (pinfunction "1_1") (pintype "passive"))
      (node (ref "SW1") (pin "B") (pinfunction "B_B") (pintype "passive"))
    )
    (net (code "44") (name "Net-(R26-Pad1)") (class "Default")
      (node (ref "R26") (pin "1") (pinfunction "1_1") (pintype "passive"))
      (node (ref "R27") (pin "2") (pinfunction "2_2") (pintype "passive"))
    )
    (net (code "45") (name "Net-(R29-Pad1)") (class "Default")
      (node (ref "R29") (pin "1") (pinfunction "1_1") (pintype "passive"))
      (node (ref "R30") (pin "2") (pinfunction "2_2") (pintype "passive"))
    )
    (net (code "46") (name "Net-(R32-Pad1)") (class "Default")
      (node (ref "R32") (pin "1") (pinfunction "1_1") (pintype "passive"))
      (node (ref "R33") (pin "2") (pinfunction "2_2") (pintype "passive"))
    )
    (net (code "47") (name "Net-(S1A-A)") (class "Default")
      (node (ref "R18") (pin "1") (pinfunction "1_1") (pintype "passive"))
      (node (ref "S1") (pin "+") (pinfunction "A_+") (pintype "passive"))
    )
    (net (code "48") (name "Net-(S2A-A)") (class "Default")
      (node (ref "R20") (pin "1") (pinfunction "1_1") (pintype "passive"))
      (node (ref "S2") (pin "+") (pinfunction "A_+") (pintype "passive"))
    )
    (net (code "49") (name "Net-(S3A-A)") (class "Default")
      (node (ref "R22") (pin "1") (pinfunction "1_1") (pintype "passive"))
      (node (ref "S3") (pin "+") (pinfunction "A_+") (pintype "passive"))
    )
    (net (code "50") (name "Net-(S4A-A)") (class "Default")
      (node (ref "R23") (pin "1") (pinfunction "1_1") (pintype "passive"))
      (node (ref "S4") (pin "+") (pinfunction "A_+") (pintype "passive"))
    )
    (net (code "51") (name "Net-(SW1B-1)") (class "Default")
      (node (ref "R19") (pin "1") (pinfunction "1_1") (pintype "passive"))
      (node (ref "R21") (pin "1") (pinfunction "1_1") (pintype "passive"))
      (node (ref "SW1") (pin "D") (pinfunction "1_D") (pintype "passive"))
    )
    (net (code "52") (name "PB_FWD") (class "Default")
      (node (ref "Q1") (pin "1") (pinfunction "G_1") (pintype "passive"))
      (node (ref "R10") (pin "2") (pinfunction "2_2") (pintype "passive"))
    )
    (net (code "53") (name "PB_MENU") (class "Default")
      (node (ref "Q4") (pin "1") (pinfunction "G_1") (pintype "passive"))
      (node (ref "R13") (pin "2") (pinfunction "2_2") (pintype "passive"))
    )
    (net (code "54") (name "PB_REV") (class "Default")
      (node (ref "Q2") (pin "1") (pinfunction "G_1") (pintype "passive"))
      (node (ref "R11") (pin "2") (pinfunction "2_2") (pintype "passive"))
    )
    (net (code "55") (name "PB_STOP") (class "Default")
      (node (ref "Q3") (pin "1") (pinfunction "G_1") (pintype "passive"))
      (node (ref "R12") (pin "2") (pinfunction "2_2") (pintype "passive"))
    )
    (net (code "56") (name "REV") (class "Default")
      (node (ref "C7") (pin "1") (pinfunction "1_1") (pintype "passive"))
      (node (ref "IC1") (pin "5") (pinfunction "P1_5") (pintype "bidirectional"))
      (node (ref "R9") (pin "1") (pinfunction "1_1") (pintype "passive"))
      (node (ref "S2") (pin "2A") (pinfunction "2_2A") (pintype "passive"))
      (node (ref "S2") (pin "2B") (pinfunction "2_2B") (pintype "passive"))
    )
    (net (code "57") (name "SCL") (class "Default")
      (node (ref "IC1") (pin "14") (pinfunction "SCL_14") (pintype "input"))
      (node (ref "X1") (pin "4") (pinfunction "S_4") (pintype "passive"))
    )
    (net (code "58") (name "SDA") (class "Default")
      (node (ref "IC1") (pin "15") (pinfunction "SDA_15") (pintype "bidirectional"))
      (node (ref "X1") (pin "3") (pinfunction "S_3") (pintype "passive"))
    )
    (net (code "59") (name "STOP") (class "Default")
      (node (ref "C6") (pin "1") (pinfunction "1_1") (pintype "passive"))
      (node (ref "IC1") (pin "6") (pinfunction "P2_6") (pintype "bidirectional"))
      (node (ref "R14") (pin "1") (pinfunction "1_1") (pintype "passive"))
      (node (ref "S3") (pin "2A") (pinfunction "2_2A") (pintype "passive"))
      (node (ref "S3") (pin "2B") (pinfunction "2_2B") (pintype "passive"))
    )
    (net (code "60") (name "UART_RX") (class "Default")
      (node (ref "X1") (pin "11") (pinfunction "S_11") (pintype "passive"))
      (node (ref "X2") (pin "2") (pinfunction "2_2") (pintype "passive"))
    )
    (net (code "61") (name "UART_TX") (class "Default")
      (node (ref "X1") (pin "12") (pinfunction "S_12") (pintype "passive"))
      (node (ref "X2") (pin "3") (pinfunction "3_3") (pintype "passive"))
    )
    (net (code "62") (name "unconnected-(H1-MOUNT-PadB3,3)") (class "Default")
      (node (ref "H1") (pin "B3,3") (pinfunction "MOUNT_B3,3") (pintype "passive"))
    )
    (net (code "63") (name "unconnected-(H2-MOUNT-PadB3,3)") (class "Default")
      (node (ref "H2") (pin "B3,3") (pinfunction "MOUNT_B3,3") (pintype "passive"))
    )
    (net (code "64") (name "unconnected-(H3-MOUNT-PadB3,3)") (class "Default")
      (node (ref "H3") (pin "B3,3") (pinfunction "MOUNT_B3,3") (pintype "passive"))
    )
    (net (code "65") (name "unconnected-(H4-MOUNT-PadB3,3)") (class "Default")
      (node (ref "H4") (pin "B3,3") (pinfunction "MOUNT_B3,3") (pintype "passive"))
    )
    (net (code "66") (name "unconnected-(IC2A-O-Pad2)") (class "Default")
      (node (ref "IC2") (pin "2") (pinfunction "O_2") (pintype "output"))
    )
    (net (code "67") (name "unconnected-(IC2B-O-Pad4)") (class "Default")
      (node (ref "IC2") (pin "4") (pinfunction "O_4") (pintype "output"))
    )
    (net (code "68") (name "~{DISP_CS}") (class "Default")
      (node (ref "M1") (pin "40") (pinfunction "~{CS1B}_40") (pintype "bidirectional"))
      (node (ref "R28") (pin "1") (pinfunction "1_1") (pintype "passive"))
      (node (ref "X1") (pin "5") (pinfunction "S_5") (pintype "passive"))
    )
    (net (code "69") (name "~{DISP_RST}") (class "Default")
      (node (ref "IC2") (pin "6") (pinfunction "O_6") (pintype "output"))
      (node (ref "M1") (pin "39") (pinfunction "~{RST}_39") (pintype "bidirectional"))
    )
    (net (code "70") (name "~{INT}") (class "Default")
      (node (ref "IC1") (pin "13") (pinfunction "~{INT}_13") (pintype "open_collector"))
      (node (ref "R3") (pin "1") (pinfunction "1_1") (pintype "passive"))
      (node (ref "X1") (pin "18") (pinfunction "S_18") (pintype "passive"))
    )
  )
)
